# rpi.net
KiCad netlist of a schematic drawn in EAGLE
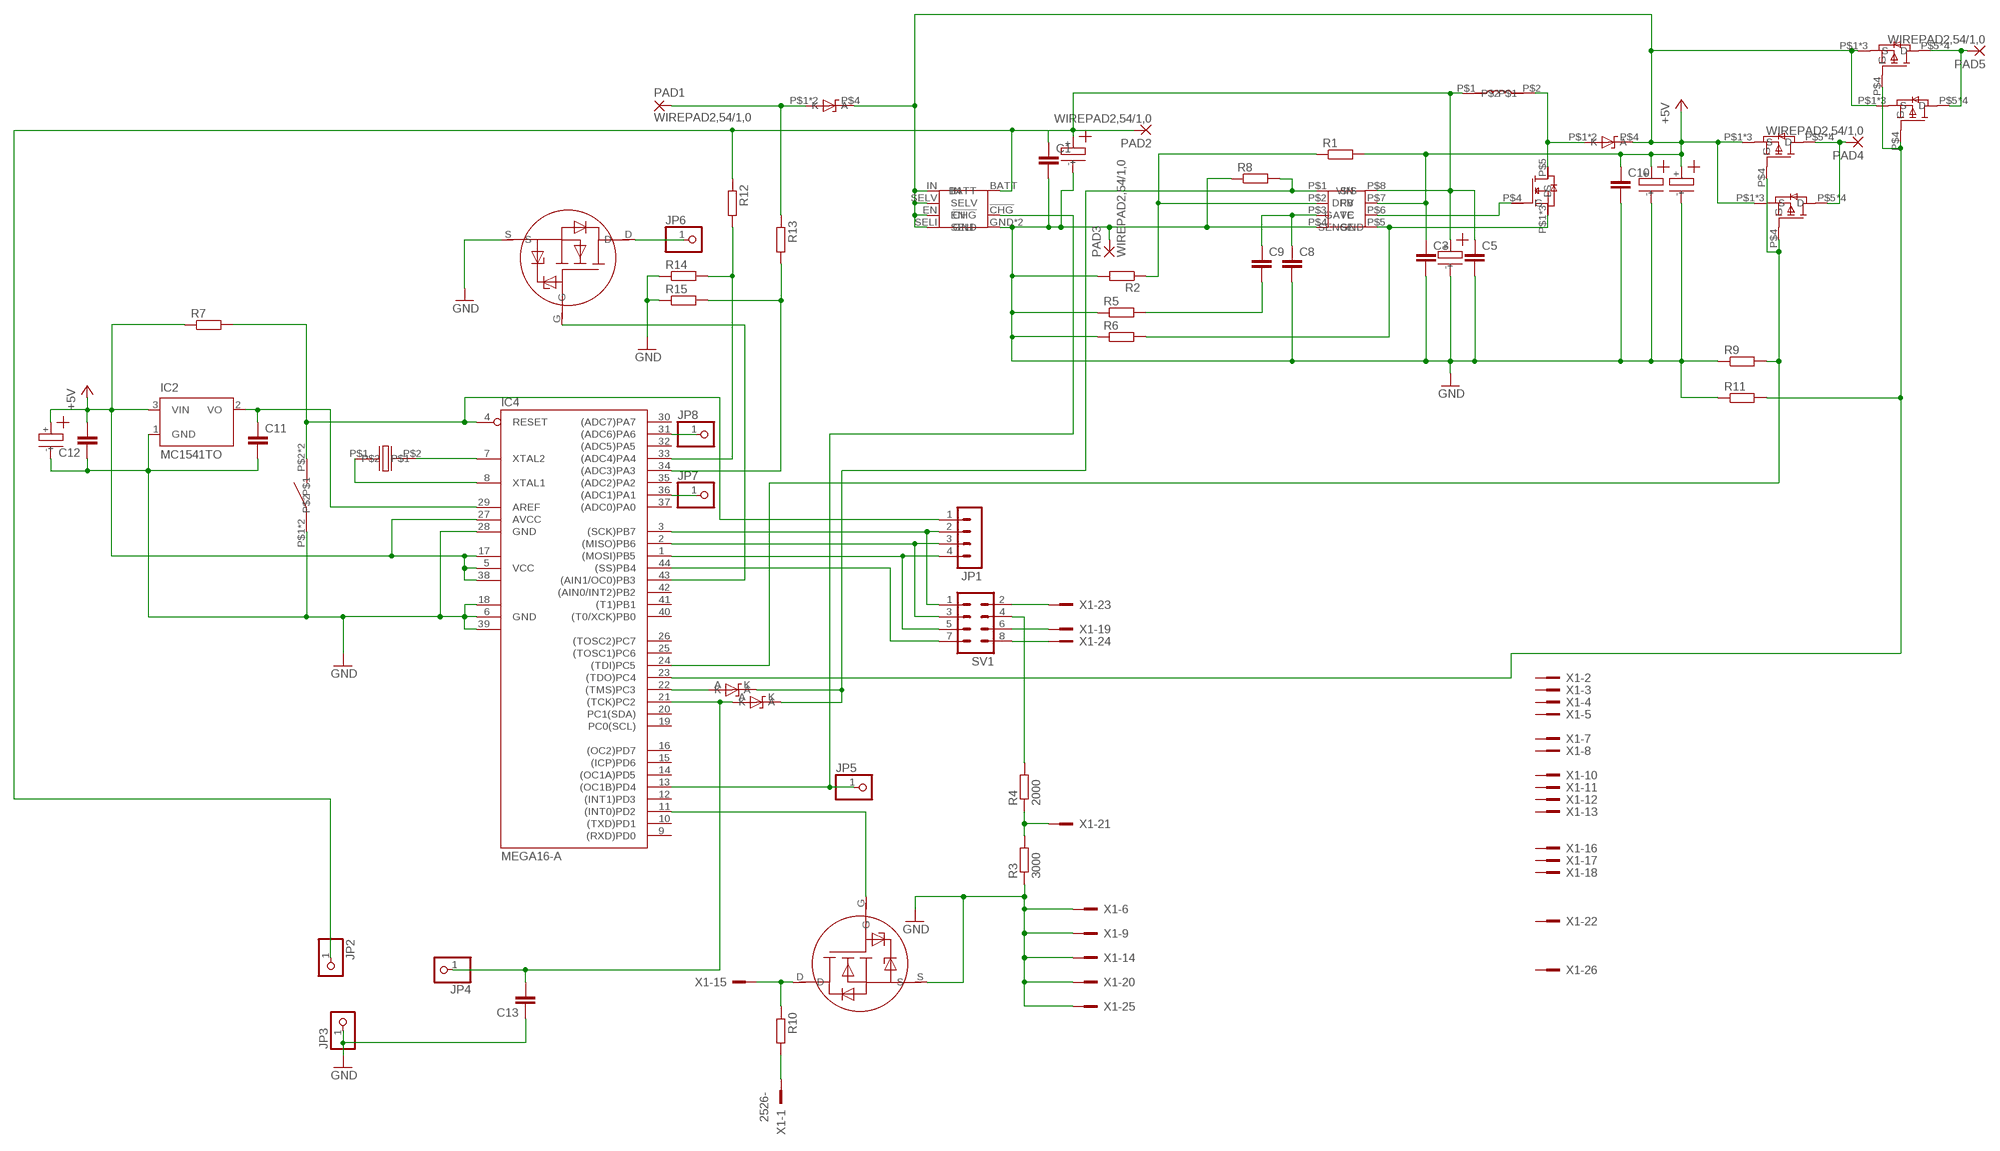
[diagram p0: schematic, sheet 1]

(export (version "E")
  (design (tool "Eeschema 10.0.6"))
  (components
    (comp (ref "C1")
      (value "C-EUC1206")
      (footprint "eagle-import:C1206")
      (libsource (lib "eagle-import") (part "C-EUC1206"))
    )
    (comp (ref "C2")
      (value "UWX0J101MCL1GB")
      (footprint "eagle-import:UWX0J101MCL1GB")
      (libsource (lib "eagle-import") (part "UWX0J101MCL1GB"))
    )
    (comp (ref "C3")
      (value "C-EUC1206")
      (footprint "eagle-import:C1206")
      (libsource (lib "eagle-import") (part "C-EUC1206"))
    )
    (comp (ref "C4")
      (value "UWX0J101MCL1GB")
      (footprint "eagle-import:UWX0J101MCL1GB")
      (libsource (lib "eagle-import") (part "UWX0J101MCL1GB"))
    )
    (comp (ref "C5")
      (value "C-EUC1206")
      (footprint "eagle-import:C1206")
      (libsource (lib "eagle-import") (part "C-EUC1206"))
    )
    (comp (ref "C6")
      (value "UWX0J101MCL1GB")
      (footprint "eagle-import:UWX0J101MCL1GB")
      (libsource (lib "eagle-import") (part "UWX0J101MCL1GB"))
    )
    (comp (ref "C7")
      (value "UWX0J101MCL1GB")
      (footprint "eagle-import:UWX0J101MCL1GB")
      (libsource (lib "eagle-import") (part "UWX0J101MCL1GB"))
    )
    (comp (ref "C8")
      (value "C-EUC1206")
      (footprint "eagle-import:C1206")
      (libsource (lib "eagle-import") (part "C-EUC1206"))
    )
    (comp (ref "C9")
      (value "C-EUC1206")
      (footprint "eagle-import:C1206")
      (libsource (lib "eagle-import") (part "C-EUC1206"))
    )
    (comp (ref "C10")
      (value "C-EUC1206")
      (footprint "eagle-import:C1206")
      (libsource (lib "eagle-import") (part "C-EUC1206"))
    )
    (comp (ref "C11")
      (value "C-EUC1206")
      (footprint "eagle-import:C1206")
      (libsource (lib "eagle-import") (part "C-EUC1206"))
    )
    (comp (ref "C12")
      (value "C-EUC1206")
      (footprint "eagle-import:C1206")
      (libsource (lib "eagle-import") (part "C-EUC1206"))
    )
    (comp (ref "C13")
      (value "C-EUC1206")
      (footprint "eagle-import:C1206")
      (libsource (lib "eagle-import") (part "C-EUC1206"))
    )
    (comp (ref "IC2")
      (value "MC1541TO")
      (footprint "eagle-import:TO92")
      (libsource (lib "eagle-import") (part "MC15TO41"))
    )
    (comp (ref "IC4")
      (value "MEGA16-A")
      (footprint "eagle-import:TQFP44")
      (fields (field (name "MPN") "ATMEGA16-16AU"))
      (libsource (lib "eagle-import") (part "MEGA16-A"))
    )
    (comp (ref "JP1")
      (value "MA04-1")
      (footprint "eagle-import:MA04-1")
      (libsource (lib "eagle-import") (part "MA04-1"))
    )
    (comp (ref "JP2")
      (value "PINHD-1X1")
      (footprint "eagle-import:1X01")
      (libsource (lib "eagle-import") (part "PINHD-1X1"))
    )
    (comp (ref "JP3")
      (value "PINHD-1X1")
      (footprint "eagle-import:1X01")
      (libsource (lib "eagle-import") (part "PINHD-1X1"))
    )
    (comp (ref "JP4")
      (value "PINHD-1X1")
      (footprint "eagle-import:1X01")
      (libsource (lib "eagle-import") (part "PINHD-1X1"))
    )
    (comp (ref "JP5")
      (value "PINHD-1X1")
      (footprint "eagle-import:1X01")
      (libsource (lib "eagle-import") (part "PINHD-1X1"))
    )
    (comp (ref "JP6")
      (value "PINHD-1X1")
      (footprint "eagle-import:1X01")
      (libsource (lib "eagle-import") (part "PINHD-1X1"))
    )
    (comp (ref "JP7")
      (value "PINHD-1X1")
      (footprint "eagle-import:1X01")
      (libsource (lib "eagle-import") (part "PINHD-1X1"))
    )
    (comp (ref "JP8")
      (value "PINHD-1X1")
      (footprint "eagle-import:1X01")
      (libsource (lib "eagle-import") (part "PINHD-1X1"))
    )
    (comp (ref "PAD1")
      (value "WIREPAD2,54/1,0")
      (footprint "eagle-import:2,54_1,0")
      (libsource (lib "eagle-import") (part "WIREPAD2,54/1,0"))
    )
    (comp (ref "PAD2")
      (value "WIREPAD2,54/1,0")
      (footprint "eagle-import:2,54_1,0")
      (libsource (lib "eagle-import") (part "WIREPAD2,54/1,0"))
    )
    (comp (ref "PAD3")
      (value "WIREPAD2,54/1,0")
      (footprint "eagle-import:2,54_1,0")
      (libsource (lib "eagle-import") (part "WIREPAD2,54/1,0"))
    )
    (comp (ref "PAD4")
      (value "WIREPAD2,54/1,0")
      (footprint "eagle-import:2,54_1,0")
      (libsource (lib "eagle-import") (part "WIREPAD2,54/1,0"))
    )
    (comp (ref "PAD5")
      (value "WIREPAD2,54/1,0")
      (footprint "eagle-import:2,54_1,0")
      (libsource (lib "eagle-import") (part "WIREPAD2,54/1,0"))
    )
    (comp (ref "R1")
      (value "R-EU_R1206")
      (footprint "eagle-import:R1206")
      (libsource (lib "eagle-import") (part "R-EU_R1206"))
    )
    (comp (ref "R2")
      (value "R-EU_R1206")
      (footprint "eagle-import:R1206")
      (libsource (lib "eagle-import") (part "R-EU_R1206"))
    )
    (comp (ref "R3")
      (value "3000")
      (footprint "eagle-import:R1206")
      (libsource (lib "eagle-import") (part "resistor_R-EU_R1206"))
    )
    (comp (ref "R4")
      (value "2000")
      (footprint "eagle-import:R1206")
      (libsource (lib "eagle-import") (part "resistor_R-EU_R1206"))
    )
    (comp (ref "R5")
      (value "R-EU_R1206")
      (footprint "eagle-import:R1206")
      (libsource (lib "eagle-import") (part "R-EU_R1206"))
    )
    (comp (ref "R6")
      (value "R-EU_R1206")
      (footprint "eagle-import:R1206")
      (libsource (lib "eagle-import") (part "R-EU_R1206"))
    )
    (comp (ref "R7")
      (value "R-EU_R1206")
      (footprint "eagle-import:R1206")
      (libsource (lib "eagle-import") (part "R-EU_R1206"))
    )
    (comp (ref "R8")
      (value "R-EU_R1206")
      (footprint "eagle-import:R1206")
      (libsource (lib "eagle-import") (part "R-EU_R1206"))
    )
    (comp (ref "R9")
      (value "R-EU_R1206")
      (footprint "eagle-import:R1206")
      (libsource (lib "eagle-import") (part "R-EU_R1206"))
    )
    (comp (ref "R10")
      (value "R-EU_R1206")
      (footprint "eagle-import:R1206")
      (libsource (lib "eagle-import") (part "R-EU_R1206"))
    )
    (comp (ref "R11")
      (value "R-EU_R1206")
      (footprint "eagle-import:R1206")
      (libsource (lib "eagle-import") (part "R-EU_R1206"))
    )
    (comp (ref "R12")
      (value "R-EU_R1206")
      (footprint "eagle-import:R1206")
      (libsource (lib "eagle-import") (part "R-EU_R1206"))
    )
    (comp (ref "R13")
      (value "R-EU_R1206")
      (footprint "eagle-import:R1206")
      (libsource (lib "eagle-import") (part "R-EU_R1206"))
    )
    (comp (ref "R14")
      (value "R-EU_R1206")
      (footprint "eagle-import:R1206")
      (libsource (lib "eagle-import") (part "R-EU_R1206"))
    )
    (comp (ref "R15")
      (value "R-EU_R1206")
      (footprint "eagle-import:R1206")
      (libsource (lib "eagle-import") (part "R-EU_R1206"))
    )
    (comp (ref "SV1")
      (value "MA04-2")
      (footprint "eagle-import:MA04-2")
      (libsource (lib "eagle-import") (part "MA04-2"))
    )
    (comp (ref "U$1")
      (value "LT1619S")
      (footprint "eagle-import:SO8")
      (libsource (lib "eagle-import") (part "LT1619S"))
    )
    (comp (ref "U$2")
      (value "NX7002AK")
      (footprint "eagle-import:SOT23")
      (libsource (lib "eagle-import") (part "NX7002AK"))
    )
    (comp (ref "U$3")
      (value "STL100NH3LL")
      (footprint "eagle-import:POWERFLAT6X5")
      (libsource (lib "eagle-import") (part "STL100NH3LL"))
    )
    (comp (ref "U$4")
      (value "MBRD835L")
      (footprint "eagle-import:DPAK")
      (libsource (lib "eagle-import") (part "MBRD835L"))
    )
    (comp (ref "U$5")
      (value "MCBF7330-5R6MU")
      (footprint "eagle-import:MCBF7330-5R6MU")
      (libsource (lib "eagle-import") (part "MCBF7330-5R6MU"))
    )
    (comp (ref "U$6")
      (value "UWX0J101MCL1GB")
      (footprint "eagle-import:UWX0J101MCL1GB")
      (libsource (lib "eagle-import") (part "UWX0J101MCL1GB"))
    )
    (comp (ref "U$7")
      (value "IRF9328PBF")
      (footprint "eagle-import:SO8")
      (libsource (lib "eagle-import") (part "IRF9328PBF"))
    )
    (comp (ref "U$8")
      (value "MAX1811")
      (footprint "eagle-import:SO8")
      (libsource (lib "eagle-import") (part "MAX1811"))
    )
    (comp (ref "U$9")
      (value "IRF9328PBF")
      (footprint "eagle-import:SO8")
      (libsource (lib "eagle-import") (part "IRF9328PBF"))
    )
    (comp (ref "U$10")
      (value "XTAL14.7456MHZ")
      (footprint "eagle-import:HC49-SMD")
      (libsource (lib "eagle-import") (part "XTAL14.7456MHZ"))
    )
    (comp (ref "U$11")
      (value "IRF9328PBF")
      (footprint "eagle-import:SO8")
      (libsource (lib "eagle-import") (part "IRF9328PBF"))
    )
    (comp (ref "U$12")
      (value "IRF9328PBF")
      (footprint "eagle-import:SO8")
      (libsource (lib "eagle-import") (part "IRF9328PBF"))
    )
    (comp (ref "U$13")
      (value "TLACITKO")
      (footprint "eagle-import:TLACITKO")
      (libsource (lib "eagle-import") (part "TLACITKO"))
    )
    (comp (ref "U$14")
      (value "NX7002AK")
      (footprint "eagle-import:SOT23")
      (libsource (lib "eagle-import") (part "NX7002AK"))
    )
    (comp (ref "U$15")
      (value "BAS0KFILM")
      (footprint "eagle-import:SOD-523")
      (libsource (lib "eagle-import") (part "BAS0KFILM"))
    )
    (comp (ref "U$16")
      (value "MBRD835L")
      (footprint "eagle-import:DPAK")
      (libsource (lib "eagle-import") (part "MBRD835L"))
    )
    (comp (ref "U$17")
      (value "BAS0KFILM")
      (footprint "eagle-import:SOD-523")
      (libsource (lib "eagle-import") (part "BAS0KFILM"))
    )
    (comp (ref "X1")
      (value "2526-")
      (footprint "eagle-import:PAK100_2500-26")
      (libsource (lib "eagle-import") (part "2526-"))
    )
  )
  (nets
    (net (code "1") (name "+5V") (class "Default")
      (node (ref "C10") (pin "1") (pinfunction "1_1") (pintype "passive"))
      (node (ref "C12") (pin "2") (pinfunction "2_2") (pintype "passive"))
      (node (ref "C3") (pin "1") (pinfunction "1_1") (pintype "passive"))
      (node (ref "C6") (pin "+") (pinfunction "+_+") (pintype "bidirectional"))
      (node (ref "C7") (pin "+") (pinfunction "+_+") (pintype "bidirectional"))
      (node (ref "IC2") (pin "3") (pinfunction "VIN_3") (pintype "input"))
      (node (ref "IC4") (pin "17") (pinfunction "VCC1_17") (pintype "power_in"))
      (node (ref "IC4") (pin "27") (pinfunction "AVCC_27") (pintype "power_in"))
      (node (ref "IC4") (pin "38") (pinfunction "VCC2_38") (pintype "power_in"))
      (node (ref "IC4") (pin "5") (pinfunction "VCC_5") (pintype "power_in"))
      (node (ref "R1") (pin "2") (pinfunction "2_2") (pintype "passive"))
      (node (ref "R7") (pin "1") (pinfunction "1_1") (pintype "passive"))
      (node (ref "U$1") (pin "P$7") (pinfunction "DRV_P$7") (pintype "bidirectional"))
      (node (ref "U$11") (pin "P$1") (pinfunction "S_P$1") (pintype "bidirectional"))
      (node (ref "U$11") (pin "P$2") (pinfunction "S_P$2") (pintype "bidirectional"))
      (node (ref "U$11") (pin "P$3") (pinfunction "S_P$3") (pintype "bidirectional"))
      (node (ref "U$12") (pin "P$1") (pinfunction "S_P$1") (pintype "bidirectional"))
      (node (ref "U$12") (pin "P$2") (pinfunction "S_P$2") (pintype "bidirectional"))
      (node (ref "U$12") (pin "P$3") (pinfunction "S_P$3") (pintype "bidirectional"))
      (node (ref "U$16") (pin "P$4") (pinfunction "K_P$4") (pintype "bidirectional"))
      (node (ref "U$4") (pin "P$4") (pinfunction "K_P$4") (pintype "bidirectional"))
      (node (ref "U$6") (pin "+") (pinfunction "+_+") (pintype "bidirectional"))
      (node (ref "U$7") (pin "P$1") (pinfunction "S_P$1") (pintype "bidirectional"))
      (node (ref "U$7") (pin "P$2") (pinfunction "S_P$2") (pintype "bidirectional"))
      (node (ref "U$7") (pin "P$3") (pinfunction "S_P$3") (pintype "bidirectional"))
      (node (ref "U$8") (pin "EN") (pinfunction "EN_EN") (pintype "bidirectional"))
      (node (ref "U$8") (pin "IN") (pinfunction "IN_IN") (pintype "bidirectional"))
      (node (ref "U$8") (pin "SELI") (pinfunction "SELI_SELI") (pintype "bidirectional"))
      (node (ref "U$8") (pin "SELV") (pinfunction "SELV_SELV") (pintype "bidirectional"))
      (node (ref "U$9") (pin "P$1") (pinfunction "S_P$1") (pintype "bidirectional"))
      (node (ref "U$9") (pin "P$2") (pinfunction "S_P$2") (pintype "bidirectional"))
      (node (ref "U$9") (pin "P$3") (pinfunction "S_P$3") (pintype "bidirectional"))
    )
    (net (code "2") (name "/XTAL1") (class "Default")
      (node (ref "IC4") (pin "8") (pinfunction "XTAL1_8") (pintype "bidirectional"))
      (node (ref "U$10") (pin "P$1") (pinfunction "P$1_P$1") (pintype "bidirectional"))
    )
    (net (code "3") (name "/XTAL2") (class "Default")
      (node (ref "IC4") (pin "7") (pinfunction "XTAL2_7") (pintype "bidirectional"))
      (node (ref "U$10") (pin "P$2") (pinfunction "P$2_P$2") (pintype "bidirectional"))
    )
    (net (code "4") (name "GND") (class "Default")
      (node (ref "C1") (pin "2") (pinfunction "2_2") (pintype "passive"))
      (node (ref "C10") (pin "2") (pinfunction "2_2") (pintype "passive"))
      (node (ref "C11") (pin "2") (pinfunction "2_2") (pintype "passive"))
      (node (ref "C12") (pin "1") (pinfunction "1_1") (pintype "passive"))
      (node (ref "C13") (pin "1") (pinfunction "1_1") (pintype "passive"))
      (node (ref "C2") (pin "-") (pinfunction "-_-") (pintype "bidirectional"))
      (node (ref "C3") (pin "2") (pinfunction "2_2") (pintype "passive"))
      (node (ref "C4") (pin "-") (pinfunction "-_-") (pintype "bidirectional"))
      (node (ref "C5") (pin "2") (pinfunction "2_2") (pintype "passive"))
      (node (ref "C6") (pin "-") (pinfunction "-_-") (pintype "bidirectional"))
      (node (ref "C7") (pin "-") (pinfunction "-_-") (pintype "bidirectional"))
      (node (ref "C8") (pin "2") (pinfunction "2_2") (pintype "passive"))
      (node (ref "IC2") (pin "1") (pinfunction "GND_1") (pintype "passive"))
      (node (ref "IC4") (pin "18") (pinfunction "GND1_18") (pintype "power_in"))
      (node (ref "IC4") (pin "28") (pinfunction "GND_28") (pintype "power_in"))
      (node (ref "IC4") (pin "39") (pinfunction "GND2_39") (pintype "power_in"))
      (node (ref "IC4") (pin "6") (pinfunction "GND_6") (pintype "power_in"))
      (node (ref "JP3") (pin "1") (pinfunction "1_1") (pintype "passive"))
      (node (ref "PAD3") (pin "1") (pinfunction "P_1") (pintype "passive"))
      (node (ref "R11") (pin "1") (pinfunction "1_1") (pintype "passive"))
      (node (ref "R14") (pin "1") (pinfunction "1_1") (pintype "passive"))
      (node (ref "R15") (pin "1") (pinfunction "1_1") (pintype "passive"))
      (node (ref "R2") (pin "2") (pinfunction "2_2") (pintype "passive"))
      (node (ref "R3") (pin "1") (pinfunction "1_1") (pintype "passive"))
      (node (ref "R5") (pin "1") (pinfunction "1_1") (pintype "passive"))
      (node (ref "R6") (pin "1") (pinfunction "1_1") (pintype "passive"))
      (node (ref "R8") (pin "1") (pinfunction "1_1") (pintype "passive"))
      (node (ref "R9") (pin "1") (pinfunction "1_1") (pintype "passive"))
      (node (ref "U$1") (pin "P$4") (pinfunction "GND_P$4") (pintype "bidirectional"))
      (node (ref "U$13") (pin "P$1") (pinfunction "P$1_P$1") (pintype "bidirectional"))
      (node (ref "U$13") (pin "P$3") (pinfunction "P$1_P$3") (pintype "bidirectional"))
      (node (ref "U$14") (pin "S") (pinfunction "S_S") (pintype "bidirectional"))
      (node (ref "U$2") (pin "S") (pinfunction "S_S") (pintype "bidirectional"))
      (node (ref "U$6") (pin "-") (pinfunction "-_-") (pintype "bidirectional"))
      (node (ref "U$8") (pin "GND") (pinfunction "GND_GND") (pintype "bidirectional"))
      (node (ref "U$8") (pin "GND2") (pinfunction "GND_GND2") (pintype "bidirectional"))
      (node (ref "X1") (pin "14") (pinfunction "KL_14") (pintype "passive"))
      (node (ref "X1") (pin "20") (pinfunction "KL_20") (pintype "passive"))
      (node (ref "X1") (pin "25") (pinfunction "KL_25") (pintype "passive"))
      (node (ref "X1") (pin "6") (pinfunction "KL_6") (pintype "passive"))
      (node (ref "X1") (pin "9") (pinfunction "KL_9") (pintype "passive"))
    )
    (net (code "5") (name "Net-(C9-Pad2)") (class "Default")
      (node (ref "C9") (pin "2") (pinfunction "2_2") (pintype "passive"))
      (node (ref "R5") (pin "2") (pinfunction "2_2") (pintype "passive"))
    )
    (net (code "6") (name "Net-(IC2-VO)") (class "Default")
      (node (ref "C11") (pin "1") (pinfunction "1_1") (pintype "passive"))
      (node (ref "IC2") (pin "2") (pinfunction "VO_2") (pintype "output"))
      (node (ref "IC4") (pin "29") (pinfunction "AREF_29") (pintype "passive"))
    )
    (net (code "7") (name "Net-(IC4-(ADC1)PA1)") (class "Default")
      (node (ref "IC4") (pin "36") (pinfunction "(ADC1)PA1_36") (pintype "bidirectional"))
      (node (ref "JP7") (pin "1") (pinfunction "1_1") (pintype "passive"))
    )
    (net (code "8") (name "Net-(IC4-(ADC3)PA3)") (class "Default")
      (node (ref "IC4") (pin "34") (pinfunction "(ADC3)PA3_34") (pintype "bidirectional"))
      (node (ref "R13") (pin "2") (pinfunction "2_2") (pintype "passive"))
      (node (ref "R15") (pin "2") (pinfunction "2_2") (pintype "passive"))
    )
    (net (code "9") (name "Net-(IC4-(ADC4)PA4)") (class "Default")
      (node (ref "IC4") (pin "33") (pinfunction "(ADC4)PA4_33") (pintype "bidirectional"))
      (node (ref "R12") (pin "2") (pinfunction "2_2") (pintype "passive"))
      (node (ref "R14") (pin "2") (pinfunction "2_2") (pintype "passive"))
    )
    (net (code "10") (name "Net-(IC4-(ADC6)PA6)") (class "Default")
      (node (ref "IC4") (pin "31") (pinfunction "(ADC6)PA6_31") (pintype "bidirectional"))
      (node (ref "JP8") (pin "1") (pinfunction "1_1") (pintype "passive"))
    )
    (net (code "11") (name "Net-(IC4-(AIN1{slash}OC0)PB3)") (class "Default")
      (node (ref "IC4") (pin "43") (pinfunction "(AIN1/OC0)PB3_43") (pintype "bidirectional"))
      (node (ref "U$14") (pin "G") (pinfunction "G_G") (pintype "bidirectional"))
    )
    (net (code "12") (name "Net-(IC4-(INT0)PD2)") (class "Default")
      (node (ref "IC4") (pin "11") (pinfunction "(INT0)PD2_11") (pintype "bidirectional"))
      (node (ref "U$2") (pin "G") (pinfunction "G_G") (pintype "bidirectional"))
    )
    (net (code "13") (name "Net-(IC4-(MISO)PB6)") (class "Default")
      (node (ref "IC4") (pin "2") (pinfunction "(MISO)PB6_2") (pintype "bidirectional"))
      (node (ref "JP1") (pin "3") (pinfunction "3_3") (pintype "passive"))
      (node (ref "SV1") (pin "3") (pinfunction "3_3") (pintype "passive"))
    )
    (net (code "14") (name "Net-(IC4-(MOSI)PB5)") (class "Default")
      (node (ref "IC4") (pin "1") (pinfunction "(MOSI)PB5_1") (pintype "bidirectional"))
      (node (ref "JP1") (pin "4") (pinfunction "4_4") (pintype "passive"))
      (node (ref "SV1") (pin "5") (pinfunction "5_5") (pintype "passive"))
    )
    (net (code "15") (name "Net-(IC4-(OC1B)PD4)") (class "Default")
      (node (ref "IC4") (pin "13") (pinfunction "(OC1B)PD4_13") (pintype "bidirectional"))
      (node (ref "JP5") (pin "1") (pinfunction "1_1") (pintype "passive"))
      (node (ref "U$8") (pin "!CHG") (pinfunction "~{CHG}_!CHG") (pintype "bidirectional"))
    )
    (net (code "16") (name "Net-(IC4-(SCK)PB7)") (class "Default")
      (node (ref "IC4") (pin "3") (pinfunction "(SCK)PB7_3") (pintype "bidirectional"))
      (node (ref "JP1") (pin "2") (pinfunction "2_2") (pintype "passive"))
      (node (ref "SV1") (pin "1") (pinfunction "1_1") (pintype "passive"))
    )
    (net (code "17") (name "Net-(IC4-(SS)PB4)") (class "Default")
      (node (ref "IC4") (pin "44") (pinfunction "(SS)PB4_44") (pintype "bidirectional"))
      (node (ref "SV1") (pin "7") (pinfunction "7_7") (pintype "passive"))
    )
    (net (code "18") (name "Net-(IC4-(TCK)PC2)") (class "Default")
      (node (ref "C13") (pin "2") (pinfunction "2_2") (pintype "passive"))
      (node (ref "IC4") (pin "21") (pinfunction "(TCK)PC2_21") (pintype "bidirectional"))
      (node (ref "JP4") (pin "1") (pinfunction "1_1") (pintype "passive"))
      (node (ref "U$17") (pin "A") (pinfunction "A_A") (pintype "bidirectional"))
    )
    (net (code "19") (name "Net-(IC4-(TDI)PC5)") (class "Default")
      (node (ref "IC4") (pin "24") (pinfunction "(TDI)PC5_24") (pintype "bidirectional"))
      (node (ref "R9") (pin "2") (pinfunction "2_2") (pintype "passive"))
      (node (ref "U$11") (pin "P$4") (pinfunction "G_P$4") (pintype "bidirectional"))
      (node (ref "U$7") (pin "P$4") (pinfunction "G_P$4") (pintype "bidirectional"))
    )
    (net (code "20") (name "Net-(IC4-(TDO)PC4)") (class "Default")
      (node (ref "IC4") (pin "23") (pinfunction "(TDO)PC4_23") (pintype "bidirectional"))
      (node (ref "R11") (pin "2") (pinfunction "2_2") (pintype "passive"))
      (node (ref "U$12") (pin "P$4") (pinfunction "G_P$4") (pintype "bidirectional"))
      (node (ref "U$9") (pin "P$4") (pinfunction "G_P$4") (pintype "bidirectional"))
    )
    (net (code "21") (name "Net-(IC4-(TMS)PC3)") (class "Default")
      (node (ref "IC4") (pin "22") (pinfunction "(TMS)PC3_22") (pintype "bidirectional"))
      (node (ref "U$15") (pin "A") (pinfunction "A_A") (pintype "bidirectional"))
    )
    (net (code "22") (name "Net-(IC4-RESET)") (class "Default")
      (node (ref "IC4") (pin "4") (pinfunction "RESET_4") (pintype "input"))
      (node (ref "JP1") (pin "1") (pinfunction "1_1") (pintype "passive"))
      (node (ref "R7") (pin "2") (pinfunction "2_2") (pintype "passive"))
      (node (ref "U$13") (pin "P$2") (pinfunction "P$2_P$2") (pintype "bidirectional"))
      (node (ref "U$13") (pin "P$4") (pinfunction "P$2_P$4") (pintype "bidirectional"))
    )
    (net (code "23") (name "Net-(JP6-Pad1)") (class "Default")
      (node (ref "JP6") (pin "1") (pinfunction "1_1") (pintype "passive"))
      (node (ref "U$14") (pin "D") (pinfunction "D_D") (pintype "bidirectional"))
    )
    (net (code "24") (name "Net-(PAD1-P)") (class "Default")
      (node (ref "PAD1") (pin "1") (pinfunction "P_1") (pintype "passive"))
      (node (ref "R13") (pin "1") (pinfunction "1_1") (pintype "passive"))
      (node (ref "U$16") (pin "P$1") (pinfunction "A_P$1") (pintype "bidirectional"))
      (node (ref "U$16") (pin "P$3") (pinfunction "A_P$3") (pintype "bidirectional"))
    )
    (net (code "25") (name "Net-(PAD2-P)") (class "Default")
      (node (ref "C1") (pin "1") (pinfunction "1_1") (pintype "passive"))
      (node (ref "C2") (pin "+") (pinfunction "+_+") (pintype "bidirectional"))
      (node (ref "C4") (pin "+") (pinfunction "+_+") (pintype "bidirectional"))
      (node (ref "C5") (pin "1") (pinfunction "1_1") (pintype "passive"))
      (node (ref "JP2") (pin "1") (pinfunction "1_1") (pintype "passive"))
      (node (ref "PAD2") (pin "1") (pinfunction "P_1") (pintype "passive"))
      (node (ref "R12") (pin "1") (pinfunction "1_1") (pintype "passive"))
      (node (ref "U$1") (pin "P$8") (pinfunction "VIN_P$8") (pintype "bidirectional"))
      (node (ref "U$5") (pin "P$1") (pinfunction "P$1_P$1") (pintype "bidirectional"))
      (node (ref "U$8") (pin "BATT") (pinfunction "BATT_BATT") (pintype "bidirectional"))
    )
    (net (code "26") (name "Net-(PAD4-P)") (class "Default")
      (node (ref "PAD4") (pin "1") (pinfunction "P_1") (pintype "passive"))
      (node (ref "U$11") (pin "P$5") (pinfunction "D_P$5") (pintype "bidirectional"))
      (node (ref "U$11") (pin "P$6") (pinfunction "D_P$6") (pintype "bidirectional"))
      (node (ref "U$11") (pin "P$7") (pinfunction "D_P$7") (pintype "bidirectional"))
      (node (ref "U$11") (pin "P$8") (pinfunction "D_P$8") (pintype "bidirectional"))
      (node (ref "U$7") (pin "P$5") (pinfunction "D_P$5") (pintype "bidirectional"))
      (node (ref "U$7") (pin "P$6") (pinfunction "D_P$6") (pintype "bidirectional"))
      (node (ref "U$7") (pin "P$7") (pinfunction "D_P$7") (pintype "bidirectional"))
      (node (ref "U$7") (pin "P$8") (pinfunction "D_P$8") (pintype "bidirectional"))
    )
    (net (code "27") (name "Net-(PAD5-P)") (class "Default")
      (node (ref "PAD5") (pin "1") (pinfunction "P_1") (pintype "passive"))
      (node (ref "U$12") (pin "P$5") (pinfunction "D_P$5") (pintype "bidirectional"))
      (node (ref "U$12") (pin "P$6") (pinfunction "D_P$6") (pintype "bidirectional"))
      (node (ref "U$12") (pin "P$7") (pinfunction "D_P$7") (pintype "bidirectional"))
      (node (ref "U$12") (pin "P$8") (pinfunction "D_P$8") (pintype "bidirectional"))
      (node (ref "U$9") (pin "P$5") (pinfunction "D_P$5") (pintype "bidirectional"))
      (node (ref "U$9") (pin "P$6") (pinfunction "D_P$6") (pintype "bidirectional"))
      (node (ref "U$9") (pin "P$7") (pinfunction "D_P$7") (pintype "bidirectional"))
      (node (ref "U$9") (pin "P$8") (pinfunction "D_P$8") (pintype "bidirectional"))
    )
    (net (code "28") (name "Net-(R4-Pad2)") (class "Default")
      (node (ref "R4") (pin "2") (pinfunction "2_2") (pintype "passive"))
      (node (ref "SV1") (pin "4") (pinfunction "4_4") (pintype "passive"))
    )
    (net (code "29") (name "Net-(U$1-FB)") (class "Default")
      (node (ref "R1") (pin "1") (pinfunction "1_1") (pintype "passive"))
      (node (ref "R2") (pin "1") (pinfunction "1_1") (pintype "passive"))
      (node (ref "U$1") (pin "P$2") (pinfunction "FB_P$2") (pintype "bidirectional"))
    )
    (net (code "30") (name "Net-(U$1-GATE)") (class "Default")
      (node (ref "U$1") (pin "P$6") (pinfunction "GATE_P$6") (pintype "bidirectional"))
      (node (ref "U$3") (pin "P$4") (pinfunction "G_P$4") (pintype "bidirectional"))
    )
    (net (code "31") (name "Net-(U$1-SENSE)") (class "Default")
      (node (ref "R6") (pin "2") (pinfunction "2_2") (pintype "passive"))
      (node (ref "U$1") (pin "P$5") (pinfunction "SENSE_P$5") (pintype "bidirectional"))
      (node (ref "U$3") (pin "P$1") (pinfunction "S_P$1") (pintype "bidirectional"))
      (node (ref "U$3") (pin "P$2") (pinfunction "S_P$2") (pintype "bidirectional"))
      (node (ref "U$3") (pin "P$3") (pinfunction "S_P$3") (pintype "bidirectional"))
    )
    (net (code "32") (name "Net-(U$1-S{slash}S)") (class "Default")
      (node (ref "R8") (pin "2") (pinfunction "2_2") (pintype "passive"))
      (node (ref "U$1") (pin "P$1") (pinfunction "S/S_P$1") (pintype "bidirectional"))
      (node (ref "U$15") (pin "K") (pinfunction "K_K") (pintype "bidirectional"))
      (node (ref "U$17") (pin "K") (pinfunction "K_K") (pintype "bidirectional"))
    )
    (net (code "33") (name "Net-(U$1-VC)") (class "Default")
      (node (ref "C8") (pin "1") (pinfunction "1_1") (pintype "passive"))
      (node (ref "C9") (pin "1") (pinfunction "1_1") (pintype "passive"))
      (node (ref "U$1") (pin "P$3") (pinfunction "VC_P$3") (pintype "bidirectional"))
    )
    (net (code "34") (name "Net-(U$3-D)") (class "Default")
      (node (ref "U$3") (pin "P$5") (pinfunction "D_P$5") (pintype "bidirectional"))
      (node (ref "U$4") (pin "P$1") (pinfunction "A_P$1") (pintype "bidirectional"))
      (node (ref "U$4") (pin "P$3") (pinfunction "A_P$3") (pintype "bidirectional"))
      (node (ref "U$5") (pin "P$2") (pinfunction "P$2_P$2") (pintype "bidirectional"))
    )
    (net (code "35") (name "Net-(X1A-KL)") (class "Default")
      (node (ref "R10") (pin "2") (pinfunction "2_2") (pintype "passive"))
      (node (ref "X1") (pin "1") (pinfunction "KL_1") (pintype "passive"))
    )
    (net (code "36") (name "Net-(X1G-KL)") (class "Default")
      (node (ref "R10") (pin "1") (pinfunction "1_1") (pintype "passive"))
      (node (ref "U$2") (pin "D") (pinfunction "D_D") (pintype "bidirectional"))
      (node (ref "X1") (pin "15") (pinfunction "KL_15") (pintype "passive"))
    )
    (net (code "37") (name "Net-(X1K-KL)") (class "Default")
      (node (ref "SV1") (pin "6") (pinfunction "6_6") (pintype "passive"))
      (node (ref "X1") (pin "19") (pinfunction "KL_19") (pintype "passive"))
    )
    (net (code "38") (name "Net-(X1N-KL)") (class "Default")
      (node (ref "R3") (pin "2") (pinfunction "2_2") (pintype "passive"))
      (node (ref "R4") (pin "1") (pinfunction "1_1") (pintype "passive"))
      (node (ref "X1") (pin "21") (pinfunction "KL_21") (pintype "passive"))
    )
    (net (code "39") (name "Net-(X1P-KL)") (class "Default")
      (node (ref "SV1") (pin "2") (pinfunction "2_2") (pintype "passive"))
      (node (ref "X1") (pin "23") (pinfunction "KL_23") (pintype "passive"))
    )
    (net (code "40") (name "Net-(X1Q-KL)") (class "Default")
      (node (ref "SV1") (pin "8") (pinfunction "8_8") (pintype "passive"))
      (node (ref "X1") (pin "24") (pinfunction "KL_24") (pintype "passive"))
    )
    (net (code "41") (name "unconnected-(IC4-(ADC0)PA0-Pad37)") (class "Default")
      (node (ref "IC4") (pin "37") (pinfunction "(ADC0)PA0_37") (pintype "bidirectional"))
    )
    (net (code "42") (name "unconnected-(IC4-(ADC2)PA2-Pad35)") (class "Default")
      (node (ref "IC4") (pin "35") (pinfunction "(ADC2)PA2_35") (pintype "bidirectional"))
    )
    (net (code "43") (name "unconnected-(IC4-(ADC5)PA5-Pad32)") (class "Default")
      (node (ref "IC4") (pin "32") (pinfunction "(ADC5)PA5_32") (pintype "bidirectional"))
    )
    (net (code "44") (name "unconnected-(IC4-(ADC7)PA7-Pad30)") (class "Default")
      (node (ref "IC4") (pin "30") (pinfunction "(ADC7)PA7_30") (pintype "bidirectional"))
    )
    (net (code "45") (name "unconnected-(IC4-(AIN0{slash}INT2)PB2-Pad42)") (class "Default")
      (node (ref "IC4") (pin "42") (pinfunction "(AIN0/INT2)PB2_42") (pintype "bidirectional"))
    )
    (net (code "46") (name "unconnected-(IC4-(ICP)PD6-Pad15)") (class "Default")
      (node (ref "IC4") (pin "15") (pinfunction "(ICP)PD6_15") (pintype "bidirectional"))
    )
    (net (code "47") (name "unconnected-(IC4-(INT1)PD3-Pad12)") (class "Default")
      (node (ref "IC4") (pin "12") (pinfunction "(INT1)PD3_12") (pintype "bidirectional"))
    )
    (net (code "48") (name "unconnected-(IC4-(OC1A)PD5-Pad14)") (class "Default")
      (node (ref "IC4") (pin "14") (pinfunction "(OC1A)PD5_14") (pintype "bidirectional"))
    )
    (net (code "49") (name "unconnected-(IC4-(OC2)PD7-Pad16)") (class "Default")
      (node (ref "IC4") (pin "16") (pinfunction "(OC2)PD7_16") (pintype "bidirectional"))
    )
    (net (code "50") (name "unconnected-(IC4-(RXD)PD0-Pad9)") (class "Default")
      (node (ref "IC4") (pin "9") (pinfunction "(RXD)PD0_9") (pintype "bidirectional"))
    )
    (net (code "51") (name "unconnected-(IC4-(T0{slash}XCK)PB0-Pad40)") (class "Default")
      (node (ref "IC4") (pin "40") (pinfunction "(T0/XCK)PB0_40") (pintype "bidirectional"))
    )
    (net (code "52") (name "unconnected-(IC4-(T1)PB1-Pad41)") (class "Default")
      (node (ref "IC4") (pin "41") (pinfunction "(T1)PB1_41") (pintype "bidirectional"))
    )
    (net (code "53") (name "unconnected-(IC4-(TOSC1)PC6-Pad25)") (class "Default")
      (node (ref "IC4") (pin "25") (pinfunction "(TOSC1)PC6_25") (pintype "bidirectional"))
    )
    (net (code "54") (name "unconnected-(IC4-(TOSC2)PC7-Pad26)") (class "Default")
      (node (ref "IC4") (pin "26") (pinfunction "(TOSC2)PC7_26") (pintype "bidirectional"))
    )
    (net (code "55") (name "unconnected-(IC4-(TXD)PD1-Pad10)") (class "Default")
      (node (ref "IC4") (pin "10") (pinfunction "(TXD)PD1_10") (pintype "bidirectional"))
    )
    (net (code "56") (name "unconnected-(IC4-PC0(SCL)-Pad19)") (class "Default")
      (node (ref "IC4") (pin "19") (pinfunction "PC0(SCL)_19") (pintype "bidirectional"))
    )
    (net (code "57") (name "unconnected-(IC4-PC1(SDA)-Pad20)") (class "Default")
      (node (ref "IC4") (pin "20") (pinfunction "PC1(SDA)_20") (pintype "bidirectional"))
    )
    (net (code "58") (name "unconnected-(X1B-KL-Pad10)") (class "Default")
      (node (ref "X1") (pin "10") (pinfunction "KL_10") (pintype "passive"))
    )
    (net (code "59") (name "unconnected-(X1C-KL-Pad11)") (class "Default")
      (node (ref "X1") (pin "11") (pinfunction "KL_11") (pintype "passive"))
    )
    (net (code "60") (name "unconnected-(X1D-KL-Pad12)") (class "Default")
      (node (ref "X1") (pin "12") (pinfunction "KL_12") (pintype "passive"))
    )
    (net (code "61") (name "unconnected-(X1E-KL-Pad13)") (class "Default")
      (node (ref "X1") (pin "13") (pinfunction "KL_13") (pintype "passive"))
    )
    (net (code "62") (name "unconnected-(X1H-KL-Pad16)") (class "Default")
      (node (ref "X1") (pin "16") (pinfunction "KL_16") (pintype "passive"))
    )
    (net (code "63") (name "unconnected-(X1I-KL-Pad17)") (class "Default")
      (node (ref "X1") (pin "17") (pinfunction "KL_17") (pintype "passive"))
    )
    (net (code "64") (name "unconnected-(X1J-KL-Pad18)") (class "Default")
      (node (ref "X1") (pin "18") (pinfunction "KL_18") (pintype "passive"))
    )
    (net (code "65") (name "unconnected-(X1L-KL-Pad2)") (class "Default")
      (node (ref "X1") (pin "2") (pinfunction "KL_2") (pintype "passive"))
    )
    (net (code "66") (name "unconnected-(X1O-KL-Pad22)") (class "Default")
      (node (ref "X1") (pin "22") (pinfunction "KL_22") (pintype "passive"))
    )
    (net (code "67") (name "unconnected-(X1S-KL-Pad26)") (class "Default")
      (node (ref "X1") (pin "26") (pinfunction "KL_26") (pintype "passive"))
    )
    (net (code "68") (name "unconnected-(X1T-KL-Pad3)") (class "Default")
      (node (ref "X1") (pin "3") (pinfunction "KL_3") (pintype "passive"))
    )
    (net (code "69") (name "unconnected-(X1U-KL-Pad4)") (class "Default")
      (node (ref "X1") (pin "4") (pinfunction "KL_4") (pintype "passive"))
    )
    (net (code "70") (name "unconnected-(X1V-KL-Pad5)") (class "Default")
      (node (ref "X1") (pin "5") (pinfunction "KL_5") (pintype "passive"))
    )
    (net (code "71") (name "unconnected-(X1X-KL-Pad7)") (class "Default")
      (node (ref "X1") (pin "7") (pinfunction "KL_7") (pintype "passive"))
    )
    (net (code "72") (name "unconnected-(X1Y-KL-Pad8)") (class "Default")
      (node (ref "X1") (pin "8") (pinfunction "KL_8") (pintype "passive"))
    )
  )
)
